# SOM_JB3.net
KiCad netlist of a schematic drawn in Altium Designer
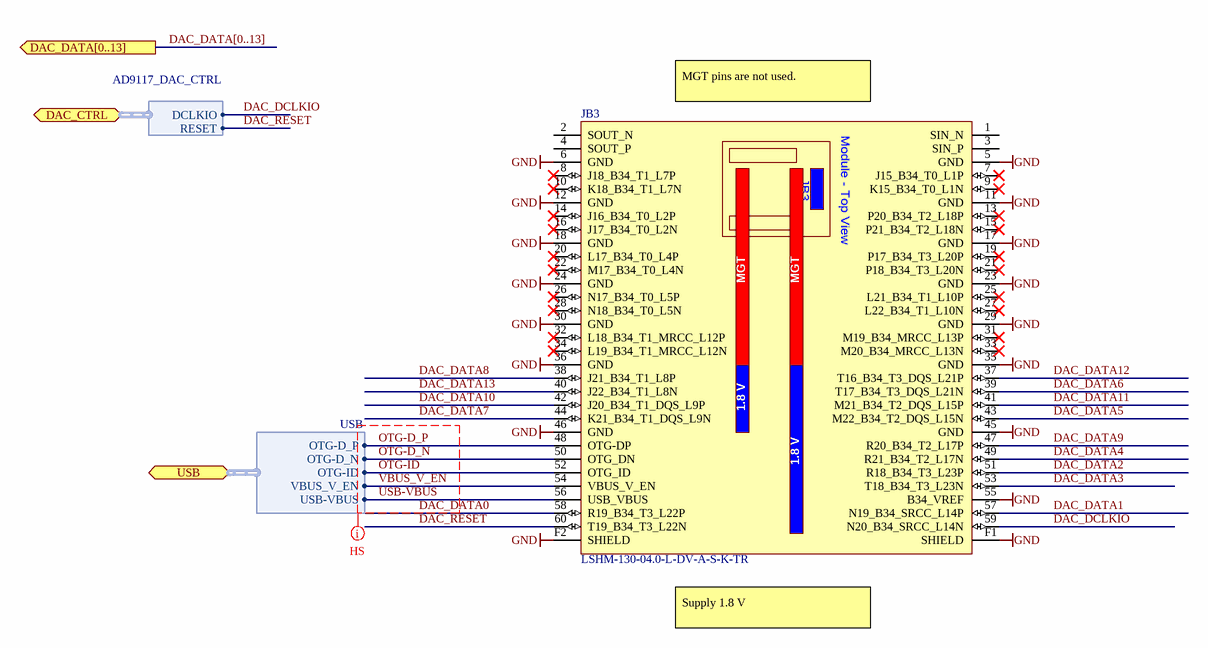
[diagram p0: SOM_JB3.SchDoc]

(export (version "E")
  (design (tool "Eeschema 10.0.6"))
  (components
    (comp (ref "JB3")
      (value "LSHM-130-04.0-L-DV-A-S-K-TR")
      (footprint "LSHM-130-04.0-x-DV-A-S-K-TR")
      (description "Samtec Razor Beam REF-189017-02, LF-04.0, 60 Pins, für alle 4x5 SoMs")
      (libsource (lib "SVPX_FMC_6U_SOM") (part "25287"))
    )
  )
  (nets
    (net (code "3") (name "/DAC_DATA0") (class "Default")
      (node (ref "JB3") (pin "58") (pinfunction "R19_B34_T3_L22P_58") (pintype "bidirectional"))
    )
    (net (code "4") (name "/DAC_DATA1") (class "Default")
      (node (ref "JB3") (pin "57") (pinfunction "N19_B34_SRCC_L14P_57") (pintype "bidirectional"))
    )
    (net (code "5") (name "/DAC_DATA2") (class "Default")
      (node (ref "JB3") (pin "51") (pinfunction "R18_B34_T3_L23P_51") (pintype "bidirectional"))
    )
    (net (code "6") (name "/DAC_DATA3") (class "Default")
      (node (ref "JB3") (pin "53") (pinfunction "T18_B34_T3_L23N_53") (pintype "bidirectional"))
    )
    (net (code "7") (name "/DAC_DATA4") (class "Default")
      (node (ref "JB3") (pin "49") (pinfunction "R21_B34_T2_L17N_49") (pintype "bidirectional"))
    )
    (net (code "8") (name "/DAC_DATA5") (class "Default")
      (node (ref "JB3") (pin "43") (pinfunction "M22_B34_T2_DQS_L15N_43") (pintype "bidirectional"))
    )
    (net (code "9") (name "/DAC_DATA6") (class "Default")
      (node (ref "JB3") (pin "39") (pinfunction "T17_B34_T3_DQS_L21N_39") (pintype "bidirectional"))
    )
    (net (code "10") (name "/DAC_DATA7") (class "Default")
      (node (ref "JB3") (pin "44") (pinfunction "K21_B34_T1_DQS_L9N_44") (pintype "bidirectional"))
    )
    (net (code "11") (name "/DAC_DATA8") (class "Default")
      (node (ref "JB3") (pin "38") (pinfunction "J21_B34_T1_L8P_38") (pintype "bidirectional"))
    )
    (net (code "12") (name "/DAC_DATA9") (class "Default")
      (node (ref "JB3") (pin "47") (pinfunction "R20_B34_T2_L17P_47") (pintype "bidirectional"))
    )
    (net (code "13") (name "/DAC_DATA10") (class "Default")
      (node (ref "JB3") (pin "42") (pinfunction "J20_B34_T1_DQS_L9P_42") (pintype "bidirectional"))
    )
    (net (code "14") (name "/DAC_DATA11") (class "Default")
      (node (ref "JB3") (pin "41") (pinfunction "M21_B34_T2_DQS_L15P_41") (pintype "bidirectional"))
    )
    (net (code "15") (name "/DAC_DATA12") (class "Default")
      (node (ref "JB3") (pin "37") (pinfunction "T16_B34_T3_DQS_L21P_37") (pintype "bidirectional"))
    )
    (net (code "16") (name "/DAC_DATA13") (class "Default")
      (node (ref "JB3") (pin "40") (pinfunction "J22_B34_T1_L8N_40") (pintype "bidirectional"))
    )
    (net (code "18") (name "/DAC_DCLKIO") (class "Default")
      (node (ref "JB3") (pin "59") (pinfunction "N20_B34_SRCC_L14N_59") (pintype "bidirectional"))
    )
    (net (code "19") (name "/DAC_RESET") (class "Default")
      (node (ref "JB3") (pin "60") (pinfunction "T19_B34_T3_L22N_60") (pintype "bidirectional"))
    )
    (net (code "20") (name "/OTG-D_N") (class "Default")
      (node (ref "JB3") (pin "50") (pinfunction "OTG_DN_50") (pintype "power_in"))
    )
    (net (code "21") (name "/OTG-D_P") (class "Default")
      (node (ref "JB3") (pin "48") (pinfunction "OTG-DP_48") (pintype "power_in"))
    )
    (net (code "22") (name "/OTG-ID") (class "Default")
      (node (ref "JB3") (pin "52") (pinfunction "OTG_ID_52") (pintype "power_in"))
    )
    (net (code "23") (name "/USB-VBUS") (class "Default")
      (node (ref "JB3") (pin "56") (pinfunction "USB_VBUS_56") (pintype "power_in"))
    )
    (net (code "24") (name "/VBUS_V_EN") (class "Default")
      (node (ref "JB3") (pin "54") (pinfunction "VBUS_V_EN_54") (pintype "power_in"))
    )
    (net (code "27") (name "GND") (class "Default")
      (node (ref "JB3") (pin "11") (pinfunction "GND_11") (pintype "power_in"))
      (node (ref "JB3") (pin "12") (pinfunction "GND_12") (pintype "power_in"))
      (node (ref "JB3") (pin "17") (pinfunction "GND_17") (pintype "power_in"))
      (node (ref "JB3") (pin "18") (pinfunction "GND_18") (pintype "power_in"))
      (node (ref "JB3") (pin "23") (pinfunction "GND_23") (pintype "power_in"))
      (node (ref "JB3") (pin "24") (pinfunction "GND_24") (pintype "power_in"))
      (node (ref "JB3") (pin "29") (pinfunction "GND_29") (pintype "power_in"))
      (node (ref "JB3") (pin "30") (pinfunction "GND_30") (pintype "power_in"))
      (node (ref "JB3") (pin "35") (pinfunction "GND_35") (pintype "power_in"))
      (node (ref "JB3") (pin "36") (pinfunction "GND_36") (pintype "power_in"))
      (node (ref "JB3") (pin "45") (pinfunction "GND_45") (pintype "power_in"))
      (node (ref "JB3") (pin "46") (pinfunction "GND_46") (pintype "power_in"))
      (node (ref "JB3") (pin "5") (pinfunction "GND_5") (pintype "power_in"))
      (node (ref "JB3") (pin "55") (pinfunction "B34_VREF_55") (pintype "power_in"))
      (node (ref "JB3") (pin "6") (pinfunction "GND_6") (pintype "power_in"))
      (node (ref "JB3") (pin "F1") (pinfunction "SHIELD_F1") (pintype "power_in"))
      (node (ref "JB3") (pin "F2") (pinfunction "SHIELD_F2") (pintype "power_in"))
    )
    (net (code "28") (name "unconnected-(JB3-J15_B34_T0_L1P-Pad7)") (class "Default")
      (node (ref "JB3") (pin "7") (pinfunction "J15_B34_T0_L1P_7") (pintype "bidirectional+no_connect"))
    )
    (net (code "29") (name "unconnected-(JB3-J16_B34_T0_L2P-Pad14)") (class "Default")
      (node (ref "JB3") (pin "14") (pinfunction "J16_B34_T0_L2P_14") (pintype "bidirectional+no_connect"))
    )
    (net (code "30") (name "unconnected-(JB3-J17_B34_T0_L2N-Pad16)") (class "Default")
      (node (ref "JB3") (pin "16") (pinfunction "J17_B34_T0_L2N_16") (pintype "bidirectional+no_connect"))
    )
    (net (code "31") (name "unconnected-(JB3-J18_B34_T1_L7P-Pad8)") (class "Default")
      (node (ref "JB3") (pin "8") (pinfunction "J18_B34_T1_L7P_8") (pintype "bidirectional+no_connect"))
    )
    (net (code "32") (name "unconnected-(JB3-K15_B34_T0_L1N-Pad9)") (class "Default")
      (node (ref "JB3") (pin "9") (pinfunction "K15_B34_T0_L1N_9") (pintype "bidirectional+no_connect"))
    )
    (net (code "33") (name "unconnected-(JB3-K18_B34_T1_L7N-Pad10)") (class "Default")
      (node (ref "JB3") (pin "10") (pinfunction "K18_B34_T1_L7N_10") (pintype "bidirectional+no_connect"))
    )
    (net (code "34") (name "unconnected-(JB3-L17_B34_T0_L4P-Pad20)") (class "Default")
      (node (ref "JB3") (pin "20") (pinfunction "L17_B34_T0_L4P_20") (pintype "bidirectional+no_connect"))
    )
    (net (code "35") (name "unconnected-(JB3-L18_B34_T1_MRCC_L12P-Pad32)") (class "Default")
      (node (ref "JB3") (pin "32") (pinfunction "L18_B34_T1_MRCC_L12P_32") (pintype "bidirectional+no_connect"))
    )
    (net (code "36") (name "unconnected-(JB3-L19_B34_T1_MRCC_L12N-Pad34)") (class "Default")
      (node (ref "JB3") (pin "34") (pinfunction "L19_B34_T1_MRCC_L12N_34") (pintype "bidirectional+no_connect"))
    )
    (net (code "37") (name "unconnected-(JB3-L21_B34_T1_L10P-Pad25)") (class "Default")
      (node (ref "JB3") (pin "25") (pinfunction "L21_B34_T1_L10P_25") (pintype "bidirectional+no_connect"))
    )
    (net (code "38") (name "unconnected-(JB3-L22_B34_T1_L10N-Pad27)") (class "Default")
      (node (ref "JB3") (pin "27") (pinfunction "L22_B34_T1_L10N_27") (pintype "bidirectional+no_connect"))
    )
    (net (code "39") (name "unconnected-(JB3-M17_B34_T0_L4N-Pad22)") (class "Default")
      (node (ref "JB3") (pin "22") (pinfunction "M17_B34_T0_L4N_22") (pintype "bidirectional+no_connect"))
    )
    (net (code "40") (name "unconnected-(JB3-M19_B34_MRCC_L13P-Pad31)") (class "Default")
      (node (ref "JB3") (pin "31") (pinfunction "M19_B34_MRCC_L13P_31") (pintype "bidirectional+no_connect"))
    )
    (net (code "41") (name "unconnected-(JB3-M20_B34_MRCC_L13N-Pad33)") (class "Default")
      (node (ref "JB3") (pin "33") (pinfunction "M20_B34_MRCC_L13N_33") (pintype "bidirectional+no_connect"))
    )
    (net (code "42") (name "unconnected-(JB3-N17_B34_T0_L5P-Pad26)") (class "Default")
      (node (ref "JB3") (pin "26") (pinfunction "N17_B34_T0_L5P_26") (pintype "bidirectional+no_connect"))
    )
    (net (code "43") (name "unconnected-(JB3-N18_B34_T0_L5N-Pad28)") (class "Default")
      (node (ref "JB3") (pin "28") (pinfunction "N18_B34_T0_L5N_28") (pintype "bidirectional+no_connect"))
    )
    (net (code "44") (name "unconnected-(JB3-P17_B34_T3_L20P-Pad19)") (class "Default")
      (node (ref "JB3") (pin "19") (pinfunction "P17_B34_T3_L20P_19") (pintype "bidirectional+no_connect"))
    )
    (net (code "45") (name "unconnected-(JB3-P18_B34_T3_L20N-Pad21)") (class "Default")
      (node (ref "JB3") (pin "21") (pinfunction "P18_B34_T3_L20N_21") (pintype "bidirectional+no_connect"))
    )
    (net (code "46") (name "unconnected-(JB3-P20_B34_T2_L18P-Pad13)") (class "Default")
      (node (ref "JB3") (pin "13") (pinfunction "P20_B34_T2_L18P_13") (pintype "bidirectional+no_connect"))
    )
    (net (code "47") (name "unconnected-(JB3-P21_B34_T2_L18N-Pad15)") (class "Default")
      (node (ref "JB3") (pin "15") (pinfunction "P21_B34_T2_L18N_15") (pintype "bidirectional+no_connect"))
    )
    (net (code "48") (name "unconnected-(JB3-SIN_N-Pad1)") (class "Default")
      (node (ref "JB3") (pin "1") (pinfunction "SIN_N_1") (pintype "power_in"))
    )
    (net (code "49") (name "unconnected-(JB3-SIN_P-Pad3)") (class "Default")
      (node (ref "JB3") (pin "3") (pinfunction "SIN_P_3") (pintype "power_in"))
    )
    (net (code "50") (name "unconnected-(JB3-SOUT_N-Pad2)") (class "Default")
      (node (ref "JB3") (pin "2") (pinfunction "SOUT_N_2") (pintype "passive"))
    )
    (net (code "51") (name "unconnected-(JB3-SOUT_P-Pad4)") (class "Default")
      (node (ref "JB3") (pin "4") (pinfunction "SOUT_P_4") (pintype "passive"))
    )
  )
)
